# Button.net
KiCad netlist of a schematic drawn in Altium Designer
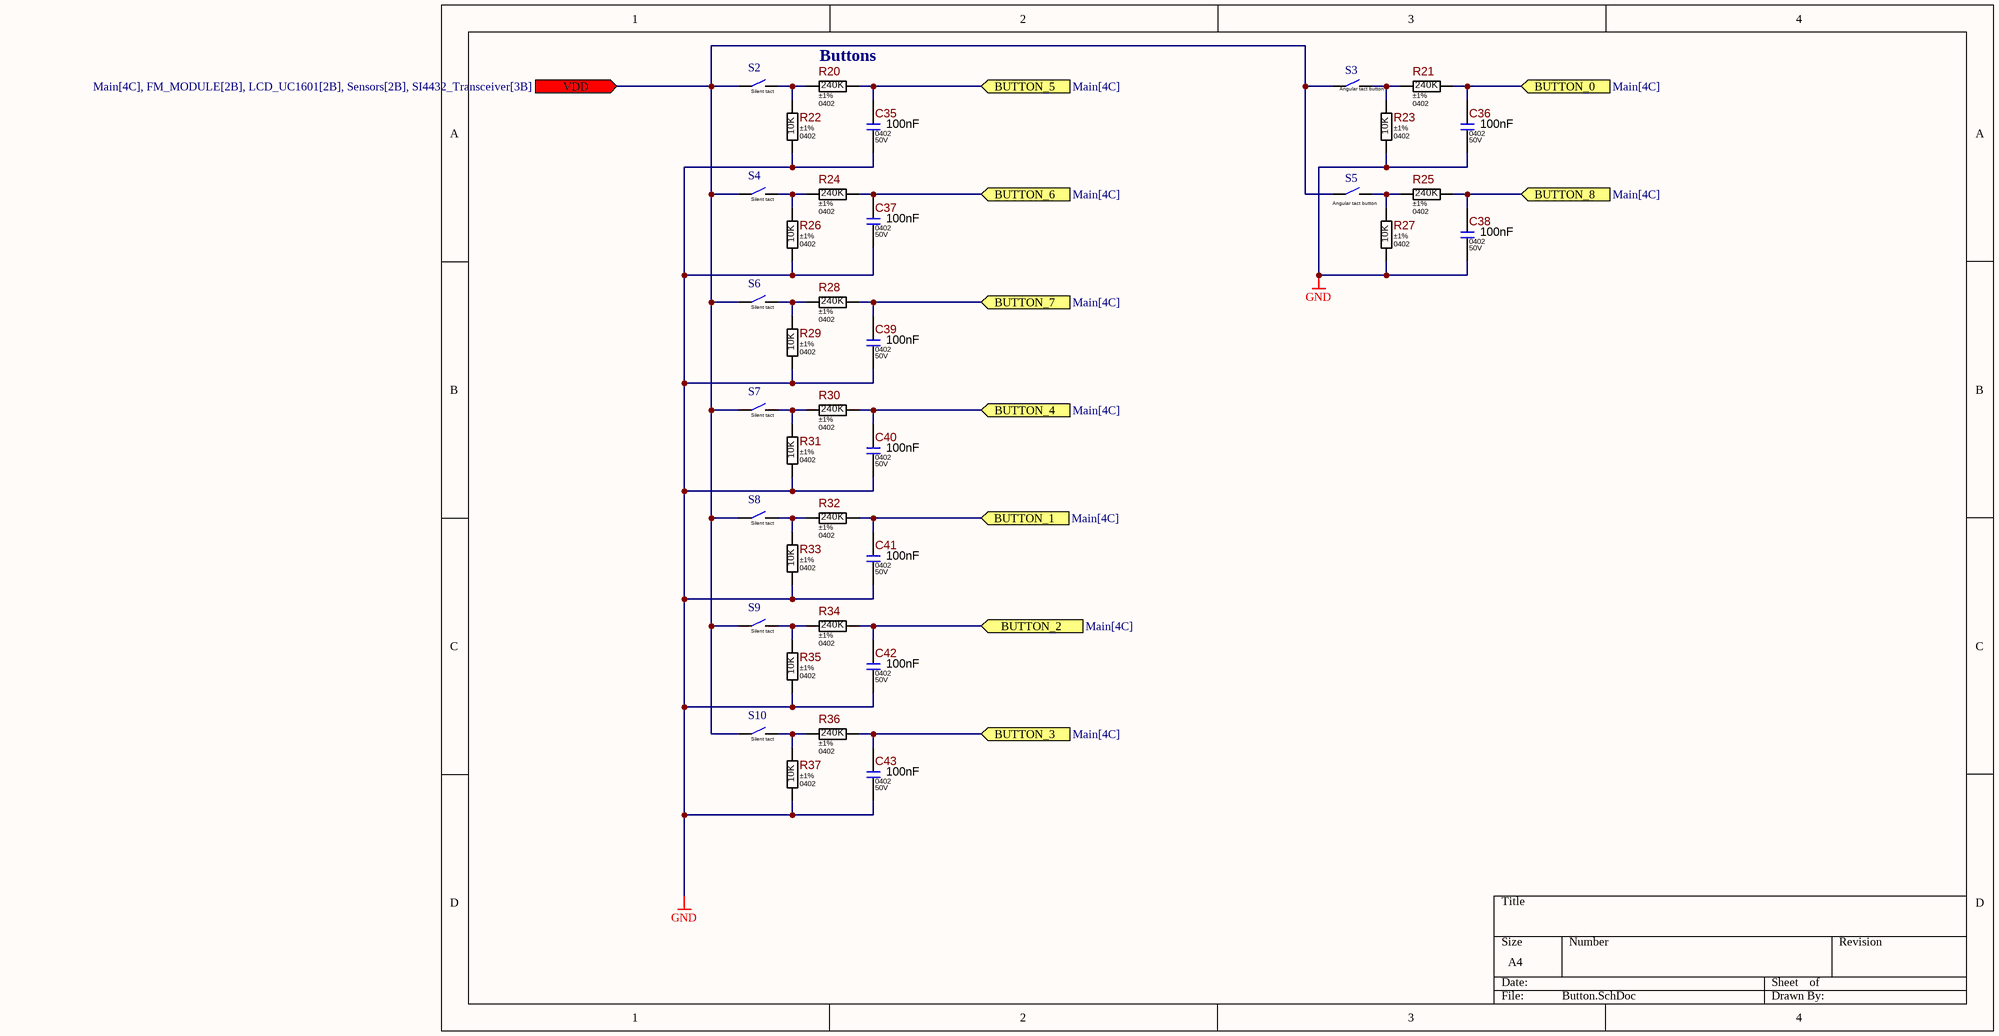
[diagram p0: Button.SchDoc]

(export (version "E")
  (design (tool "Eeschema 10.0.6"))
  (components
    (comp (ref "C35")
      (value "100nF")
      (footprint "Cap_0402")
      (description "100nF 50V  ±25% 0402 Ceramic Capacitor")
      (fields
        (field (name "TOLERANCE") "±25%")
        (field (name "PACKAGE") "0402")
        (field (name "VOLTAGE") "50V")
      )
      (libsource (lib "Capacitors") (part "Cap_0402_100nF"))
    )
    (comp (ref "C36")
      (value "100nF")
      (footprint "Cap_0402")
      (description "100nF 50V  ±25% 0402 Ceramic Capacitor")
      (fields
        (field (name "TOLERANCE") "±25%")
        (field (name "PACKAGE") "0402")
        (field (name "VOLTAGE") "50V")
      )
      (libsource (lib "Capacitors") (part "Cap_0402_100nF"))
    )
    (comp (ref "C37")
      (value "100nF")
      (footprint "Cap_0402")
      (description "100nF 50V  ±25% 0402 Ceramic Capacitor")
      (fields
        (field (name "TOLERANCE") "±25%")
        (field (name "PACKAGE") "0402")
        (field (name "VOLTAGE") "50V")
      )
      (libsource (lib "Capacitors") (part "Cap_0402_100nF"))
    )
    (comp (ref "C38")
      (value "100nF")
      (footprint "Cap_0402")
      (description "100nF 50V  ±25% 0402 Ceramic Capacitor")
      (fields
        (field (name "TOLERANCE") "±25%")
        (field (name "PACKAGE") "0402")
        (field (name "VOLTAGE") "50V")
      )
      (libsource (lib "Capacitors") (part "Cap_0402_100nF"))
    )
    (comp (ref "C39")
      (value "100nF")
      (footprint "Cap_0402")
      (description "100nF 50V  ±25% 0402 Ceramic Capacitor")
      (fields
        (field (name "TOLERANCE") "±25%")
        (field (name "PACKAGE") "0402")
        (field (name "VOLTAGE") "50V")
      )
      (libsource (lib "Capacitors") (part "Cap_0402_100nF"))
    )
    (comp (ref "C40")
      (value "100nF")
      (footprint "Cap_0402")
      (description "100nF 50V  ±25% 0402 Ceramic Capacitor")
      (fields
        (field (name "TOLERANCE") "±25%")
        (field (name "PACKAGE") "0402")
        (field (name "VOLTAGE") "50V")
      )
      (libsource (lib "Capacitors") (part "Cap_0402_100nF"))
    )
    (comp (ref "C41")
      (value "100nF")
      (footprint "Cap_0402")
      (description "100nF 50V  ±25% 0402 Ceramic Capacitor")
      (fields
        (field (name "TOLERANCE") "±25%")
        (field (name "PACKAGE") "0402")
        (field (name "VOLTAGE") "50V")
      )
      (libsource (lib "Capacitors") (part "Cap_0402_100nF"))
    )
    (comp (ref "C42")
      (value "100nF")
      (footprint "Cap_0402")
      (description "100nF 50V  ±25% 0402 Ceramic Capacitor")
      (fields
        (field (name "TOLERANCE") "±25%")
        (field (name "PACKAGE") "0402")
        (field (name "VOLTAGE") "50V")
      )
      (libsource (lib "Capacitors") (part "Cap_0402_100nF"))
    )
    (comp (ref "C43")
      (value "100nF")
      (footprint "Cap_0402")
      (description "100nF 50V  ±25% 0402 Ceramic Capacitor")
      (fields
        (field (name "TOLERANCE") "±25%")
        (field (name "PACKAGE") "0402")
        (field (name "VOLTAGE") "50V")
      )
      (libsource (lib "Capacitors") (part "Cap_0402_100nF"))
    )
    (comp (ref "R20")
      (value "240K")
      (footprint "Res_0402")
      (description "±1% 1/16W 0402")
      (fields
        (field (name "VOLTAGE") "50V")
        (field (name "TOLERANCE") "±1%")
        (field (name "PACKAGE") "0402")
        (field (name "Comment") "Res_0402_240K")
      )
      (libsource (lib "Resistors") (part "Res_0402_240K"))
    )
    (comp (ref "R21")
      (value "240K")
      (footprint "Res_0402")
      (description "±1% 1/16W 0402")
      (fields
        (field (name "VOLTAGE") "50V")
        (field (name "TOLERANCE") "±1%")
        (field (name "PACKAGE") "0402")
        (field (name "Comment") "Res_0402_240K")
      )
      (libsource (lib "Resistors") (part "Res_0402_240K"))
    )
    (comp (ref "R22")
      (value "10K")
      (footprint "Res_0402")
      (description "±1% 1/16W 0402")
      (fields
        (field (name "VOLTAGE") "50V")
        (field (name "TOLERANCE") "±1%")
        (field (name "PACKAGE") "0402")
        (field (name "Comment") "Res_0402_10K")
      )
      (libsource (lib "Resistors") (part "Res_0402_10K"))
    )
    (comp (ref "R23")
      (value "10K")
      (footprint "Res_0402")
      (description "±1% 1/16W 0402")
      (fields
        (field (name "VOLTAGE") "50V")
        (field (name "TOLERANCE") "±1%")
        (field (name "PACKAGE") "0402")
        (field (name "Comment") "Res_0402_10K")
      )
      (libsource (lib "Resistors") (part "Res_0402_10K"))
    )
    (comp (ref "R24")
      (value "240K")
      (footprint "Res_0402")
      (description "±1% 1/16W 0402")
      (fields
        (field (name "VOLTAGE") "50V")
        (field (name "TOLERANCE") "±1%")
        (field (name "PACKAGE") "0402")
        (field (name "Comment") "Res_0402_240K")
      )
      (libsource (lib "Resistors") (part "Res_0402_240K"))
    )
    (comp (ref "R25")
      (value "240K")
      (footprint "Res_0402")
      (description "±1% 1/16W 0402")
      (fields
        (field (name "VOLTAGE") "50V")
        (field (name "TOLERANCE") "±1%")
        (field (name "PACKAGE") "0402")
        (field (name "Comment") "Res_0402_240K")
      )
      (libsource (lib "Resistors") (part "Res_0402_240K"))
    )
    (comp (ref "R26")
      (value "10K")
      (footprint "Res_0402")
      (description "±1% 1/16W 0402")
      (fields
        (field (name "VOLTAGE") "50V")
        (field (name "TOLERANCE") "±1%")
        (field (name "PACKAGE") "0402")
        (field (name "Comment") "Res_0402_10K")
      )
      (libsource (lib "Resistors") (part "Res_0402_10K"))
    )
    (comp (ref "R27")
      (value "10K")
      (footprint "Res_0402")
      (description "±1% 1/16W 0402")
      (fields
        (field (name "VOLTAGE") "50V")
        (field (name "TOLERANCE") "±1%")
        (field (name "PACKAGE") "0402")
        (field (name "Comment") "Res_0402_10K")
      )
      (libsource (lib "Resistors") (part "Res_0402_10K"))
    )
    (comp (ref "R28")
      (value "240K")
      (footprint "Res_0402")
      (description "±1% 1/16W 0402")
      (fields
        (field (name "VOLTAGE") "50V")
        (field (name "TOLERANCE") "±1%")
        (field (name "PACKAGE") "0402")
        (field (name "Comment") "Res_0402_240K")
      )
      (libsource (lib "Resistors") (part "Res_0402_240K"))
    )
    (comp (ref "R29")
      (value "10K")
      (footprint "Res_0402")
      (description "±1% 1/16W 0402")
      (fields
        (field (name "VOLTAGE") "50V")
        (field (name "TOLERANCE") "±1%")
        (field (name "PACKAGE") "0402")
        (field (name "Comment") "Res_0402_10K")
      )
      (libsource (lib "Resistors") (part "Res_0402_10K"))
    )
    (comp (ref "R30")
      (value "240K")
      (footprint "Res_0402")
      (description "±1% 1/16W 0402")
      (fields
        (field (name "VOLTAGE") "50V")
        (field (name "TOLERANCE") "±1%")
        (field (name "PACKAGE") "0402")
        (field (name "Comment") "Res_0402_240K")
      )
      (libsource (lib "Resistors") (part "Res_0402_240K"))
    )
    (comp (ref "R31")
      (value "10K")
      (footprint "Res_0402")
      (description "±1% 1/16W 0402")
      (fields
        (field (name "VOLTAGE") "50V")
        (field (name "TOLERANCE") "±1%")
        (field (name "PACKAGE") "0402")
        (field (name "Comment") "Res_0402_10K")
      )
      (libsource (lib "Resistors") (part "Res_0402_10K"))
    )
    (comp (ref "R32")
      (value "240K")
      (footprint "Res_0402")
      (description "±1% 1/16W 0402")
      (fields
        (field (name "VOLTAGE") "50V")
        (field (name "TOLERANCE") "±1%")
        (field (name "PACKAGE") "0402")
        (field (name "Comment") "Res_0402_240K")
      )
      (libsource (lib "Resistors") (part "Res_0402_240K"))
    )
    (comp (ref "R33")
      (value "10K")
      (footprint "Res_0402")
      (description "±1% 1/16W 0402")
      (fields
        (field (name "VOLTAGE") "50V")
        (field (name "TOLERANCE") "±1%")
        (field (name "PACKAGE") "0402")
        (field (name "Comment") "Res_0402_10K")
      )
      (libsource (lib "Resistors") (part "Res_0402_10K"))
    )
    (comp (ref "R34")
      (value "240K")
      (footprint "Res_0402")
      (description "±1% 1/16W 0402")
      (fields
        (field (name "VOLTAGE") "50V")
        (field (name "TOLERANCE") "±1%")
        (field (name "PACKAGE") "0402")
        (field (name "Comment") "Res_0402_240K")
      )
      (libsource (lib "Resistors") (part "Res_0402_240K"))
    )
    (comp (ref "R35")
      (value "10K")
      (footprint "Res_0402")
      (description "±1% 1/16W 0402")
      (fields
        (field (name "VOLTAGE") "50V")
        (field (name "TOLERANCE") "±1%")
        (field (name "PACKAGE") "0402")
        (field (name "Comment") "Res_0402_10K")
      )
      (libsource (lib "Resistors") (part "Res_0402_10K"))
    )
    (comp (ref "R36")
      (value "240K")
      (footprint "Res_0402")
      (description "±1% 1/16W 0402")
      (fields
        (field (name "VOLTAGE") "50V")
        (field (name "TOLERANCE") "±1%")
        (field (name "PACKAGE") "0402")
        (field (name "Comment") "Res_0402_240K")
      )
      (libsource (lib "Resistors") (part "Res_0402_240K"))
    )
    (comp (ref "R37")
      (value "10K")
      (footprint "Res_0402")
      (description "±1% 1/16W 0402")
      (fields
        (field (name "VOLTAGE") "50V")
        (field (name "TOLERANCE") "±1%")
        (field (name "PACKAGE") "0402")
        (field (name "Comment") "Res_0402_10K")
      )
      (libsource (lib "Resistors") (part "Res_0402_10K"))
    )
    (comp (ref "S2")
      (value "Silent Tact Switch")
      (footprint "Tact Switch_6*6*5mm")
      (description "6*6*5mm Smd Silicone Button Switch")
      (fields (field (name "NAME") "Silent tact"))
      (libsource (lib "Button") (part "Silent Tact Switch"))
    )
    (comp (ref "S3")
      (value "Angular tact button")
      (footprint "Tact_button_3X6X3.5mm")
      (description "3X6X3.5mm")
      (fields (field (name "NAME") "Angular tact button"))
      (libsource (lib "Button") (part "Angular tact button"))
    )
    (comp (ref "S4")
      (value "Silent Tact Switch")
      (footprint "Tact Switch_6*6*5mm")
      (description "6*6*5mm Smd Silicone Button Switch")
      (fields (field (name "NAME") "Silent tact"))
      (libsource (lib "Button") (part "Silent Tact Switch"))
    )
    (comp (ref "S5")
      (value "Angular tact button")
      (footprint "Tact_button_3X6X3.5mm")
      (description "3X6X3.5mm")
      (fields (field (name "NAME") "Angular tact button"))
      (libsource (lib "Button") (part "Angular tact button"))
    )
    (comp (ref "S6")
      (value "Silent Tact Switch")
      (footprint "Tact Switch_6*6*5mm")
      (description "6*6*5mm Smd Silicone Button Switch")
      (fields (field (name "NAME") "Silent tact"))
      (libsource (lib "Button") (part "Silent Tact Switch"))
    )
    (comp (ref "S7")
      (value "Silent Tact Switch")
      (footprint "Tact Switch_6*6*5mm")
      (description "6*6*5mm Smd Silicone Button Switch")
      (fields (field (name "NAME") "Silent tact"))
      (libsource (lib "Button") (part "Silent Tact Switch"))
    )
    (comp (ref "S8")
      (value "Silent Tact Switch")
      (footprint "Tact Switch_6*6*5mm")
      (description "6*6*5mm Smd Silicone Button Switch")
      (fields (field (name "NAME") "Silent tact"))
      (libsource (lib "Button") (part "Silent Tact Switch"))
    )
    (comp (ref "S9")
      (value "Silent Tact Switch")
      (footprint "Tact Switch_6*6*5mm")
      (description "6*6*5mm Smd Silicone Button Switch")
      (fields (field (name "NAME") "Silent tact"))
      (libsource (lib "Button") (part "Silent Tact Switch"))
    )
    (comp (ref "S10")
      (value "Silent Tact Switch")
      (footprint "Tact Switch_6*6*5mm")
      (description "6*6*5mm Smd Silicone Button Switch")
      (fields (field (name "NAME") "Silent tact"))
      (libsource (lib "Button") (part "Silent Tact Switch"))
    )
  )
  (nets
    (net (code "1") (name "/BUTTON_0") (class "Default")
      (node (ref "C36") (pin "1") (pinfunction "1_1") (pintype "passive"))
      (node (ref "R21") (pin "2") (pintype "passive"))
    )
    (net (code "2") (name "/BUTTON_1") (class "Default")
      (node (ref "C41") (pin "1") (pinfunction "1_1") (pintype "passive"))
      (node (ref "R32") (pin "2") (pintype "passive"))
    )
    (net (code "3") (name "/BUTTON_2") (class "Default")
      (node (ref "C42") (pin "1") (pinfunction "1_1") (pintype "passive"))
      (node (ref "R34") (pin "2") (pintype "passive"))
    )
    (net (code "4") (name "/BUTTON_3") (class "Default")
      (node (ref "C43") (pin "1") (pinfunction "1_1") (pintype "passive"))
      (node (ref "R36") (pin "2") (pintype "passive"))
    )
    (net (code "5") (name "/BUTTON_4") (class "Default")
      (node (ref "C40") (pin "1") (pinfunction "1_1") (pintype "passive"))
      (node (ref "R30") (pin "2") (pintype "passive"))
    )
    (net (code "6") (name "/BUTTON_5") (class "Default")
      (node (ref "C35") (pin "1") (pinfunction "1_1") (pintype "passive"))
      (node (ref "R20") (pin "2") (pintype "passive"))
    )
    (net (code "7") (name "/BUTTON_6") (class "Default")
      (node (ref "C37") (pin "1") (pinfunction "1_1") (pintype "passive"))
      (node (ref "R24") (pin "2") (pintype "passive"))
    )
    (net (code "8") (name "/BUTTON_7") (class "Default")
      (node (ref "C39") (pin "1") (pinfunction "1_1") (pintype "passive"))
      (node (ref "R28") (pin "2") (pintype "passive"))
    )
    (net (code "9") (name "/BUTTON_8") (class "Default")
      (node (ref "C38") (pin "1") (pinfunction "1_1") (pintype "passive"))
      (node (ref "R25") (pin "2") (pintype "passive"))
    )
    (net (code "10") (name "/VDD") (class "Default")
      (node (ref "S10") (pin "1") (pintype "passive"))
      (node (ref "S2") (pin "1") (pintype "passive"))
      (node (ref "S3") (pin "1") (pintype "passive"))
      (node (ref "S4") (pin "1") (pintype "passive"))
      (node (ref "S5") (pin "1") (pintype "passive"))
      (node (ref "S6") (pin "1") (pintype "passive"))
      (node (ref "S7") (pin "1") (pintype "passive"))
      (node (ref "S8") (pin "1") (pintype "passive"))
      (node (ref "S9") (pin "1") (pintype "passive"))
    )
    (net (code "11") (name "GND") (class "Default")
      (node (ref "C35") (pin "2") (pinfunction "2_2") (pintype "passive"))
      (node (ref "C36") (pin "2") (pinfunction "2_2") (pintype "passive"))
      (node (ref "C37") (pin "2") (pinfunction "2_2") (pintype "passive"))
      (node (ref "C38") (pin "2") (pinfunction "2_2") (pintype "passive"))
      (node (ref "C39") (pin "2") (pinfunction "2_2") (pintype "passive"))
      (node (ref "C40") (pin "2") (pinfunction "2_2") (pintype "passive"))
      (node (ref "C41") (pin "2") (pinfunction "2_2") (pintype "passive"))
      (node (ref "C42") (pin "2") (pinfunction "2_2") (pintype "passive"))
      (node (ref "C43") (pin "2") (pinfunction "2_2") (pintype "passive"))
      (node (ref "R22") (pin "2") (pintype "passive"))
      (node (ref "R23") (pin "2") (pintype "passive"))
      (node (ref "R26") (pin "2") (pintype "passive"))
      (node (ref "R27") (pin "2") (pintype "passive"))
      (node (ref "R29") (pin "2") (pintype "passive"))
      (node (ref "R31") (pin "2") (pintype "passive"))
      (node (ref "R33") (pin "2") (pintype "passive"))
      (node (ref "R35") (pin "2") (pintype "passive"))
      (node (ref "R37") (pin "2") (pintype "passive"))
    )
    (net (code "12") (name "Net-(R20-Pad1)") (class "Default")
      (node (ref "R20") (pin "1") (pintype "passive"))
      (node (ref "R22") (pin "1") (pintype "passive"))
      (node (ref "S2") (pin "2") (pintype "passive"))
    )
    (net (code "13") (name "Net-(R21-Pad1)") (class "Default")
      (node (ref "R21") (pin "1") (pintype "passive"))
      (node (ref "R23") (pin "1") (pintype "passive"))
      (node (ref "S3") (pin "2") (pintype "passive"))
    )
    (net (code "14") (name "Net-(R24-Pad1)") (class "Default")
      (node (ref "R24") (pin "1") (pintype "passive"))
      (node (ref "R26") (pin "1") (pintype "passive"))
      (node (ref "S4") (pin "2") (pintype "passive"))
    )
    (net (code "15") (name "Net-(R25-Pad1)") (class "Default")
      (node (ref "R25") (pin "1") (pintype "passive"))
      (node (ref "R27") (pin "1") (pintype "passive"))
      (node (ref "S5") (pin "2") (pintype "passive"))
    )
    (net (code "16") (name "Net-(R28-Pad1)") (class "Default")
      (node (ref "R28") (pin "1") (pintype "passive"))
      (node (ref "R29") (pin "1") (pintype "passive"))
      (node (ref "S6") (pin "2") (pintype "passive"))
    )
    (net (code "17") (name "Net-(R30-Pad1)") (class "Default")
      (node (ref "R30") (pin "1") (pintype "passive"))
      (node (ref "R31") (pin "1") (pintype "passive"))
      (node (ref "S7") (pin "2") (pintype "passive"))
    )
    (net (code "18") (name "Net-(R32-Pad1)") (class "Default")
      (node (ref "R32") (pin "1") (pintype "passive"))
      (node (ref "R33") (pin "1") (pintype "passive"))
      (node (ref "S8") (pin "2") (pintype "passive"))
    )
    (net (code "19") (name "Net-(R34-Pad1)") (class "Default")
      (node (ref "R34") (pin "1") (pintype "passive"))
      (node (ref "R35") (pin "1") (pintype "passive"))
      (node (ref "S9") (pin "2") (pintype "passive"))
    )
    (net (code "20") (name "Net-(R36-Pad1)") (class "Default")
      (node (ref "R36") (pin "1") (pintype "passive"))
      (node (ref "R37") (pin "1") (pintype "passive"))
      (node (ref "S10") (pin "2") (pintype "passive"))
    )
  )
)
